# HRT_D_ER100_V1_0.net
KiCad netlist of a schematic drawn in Altium Designer
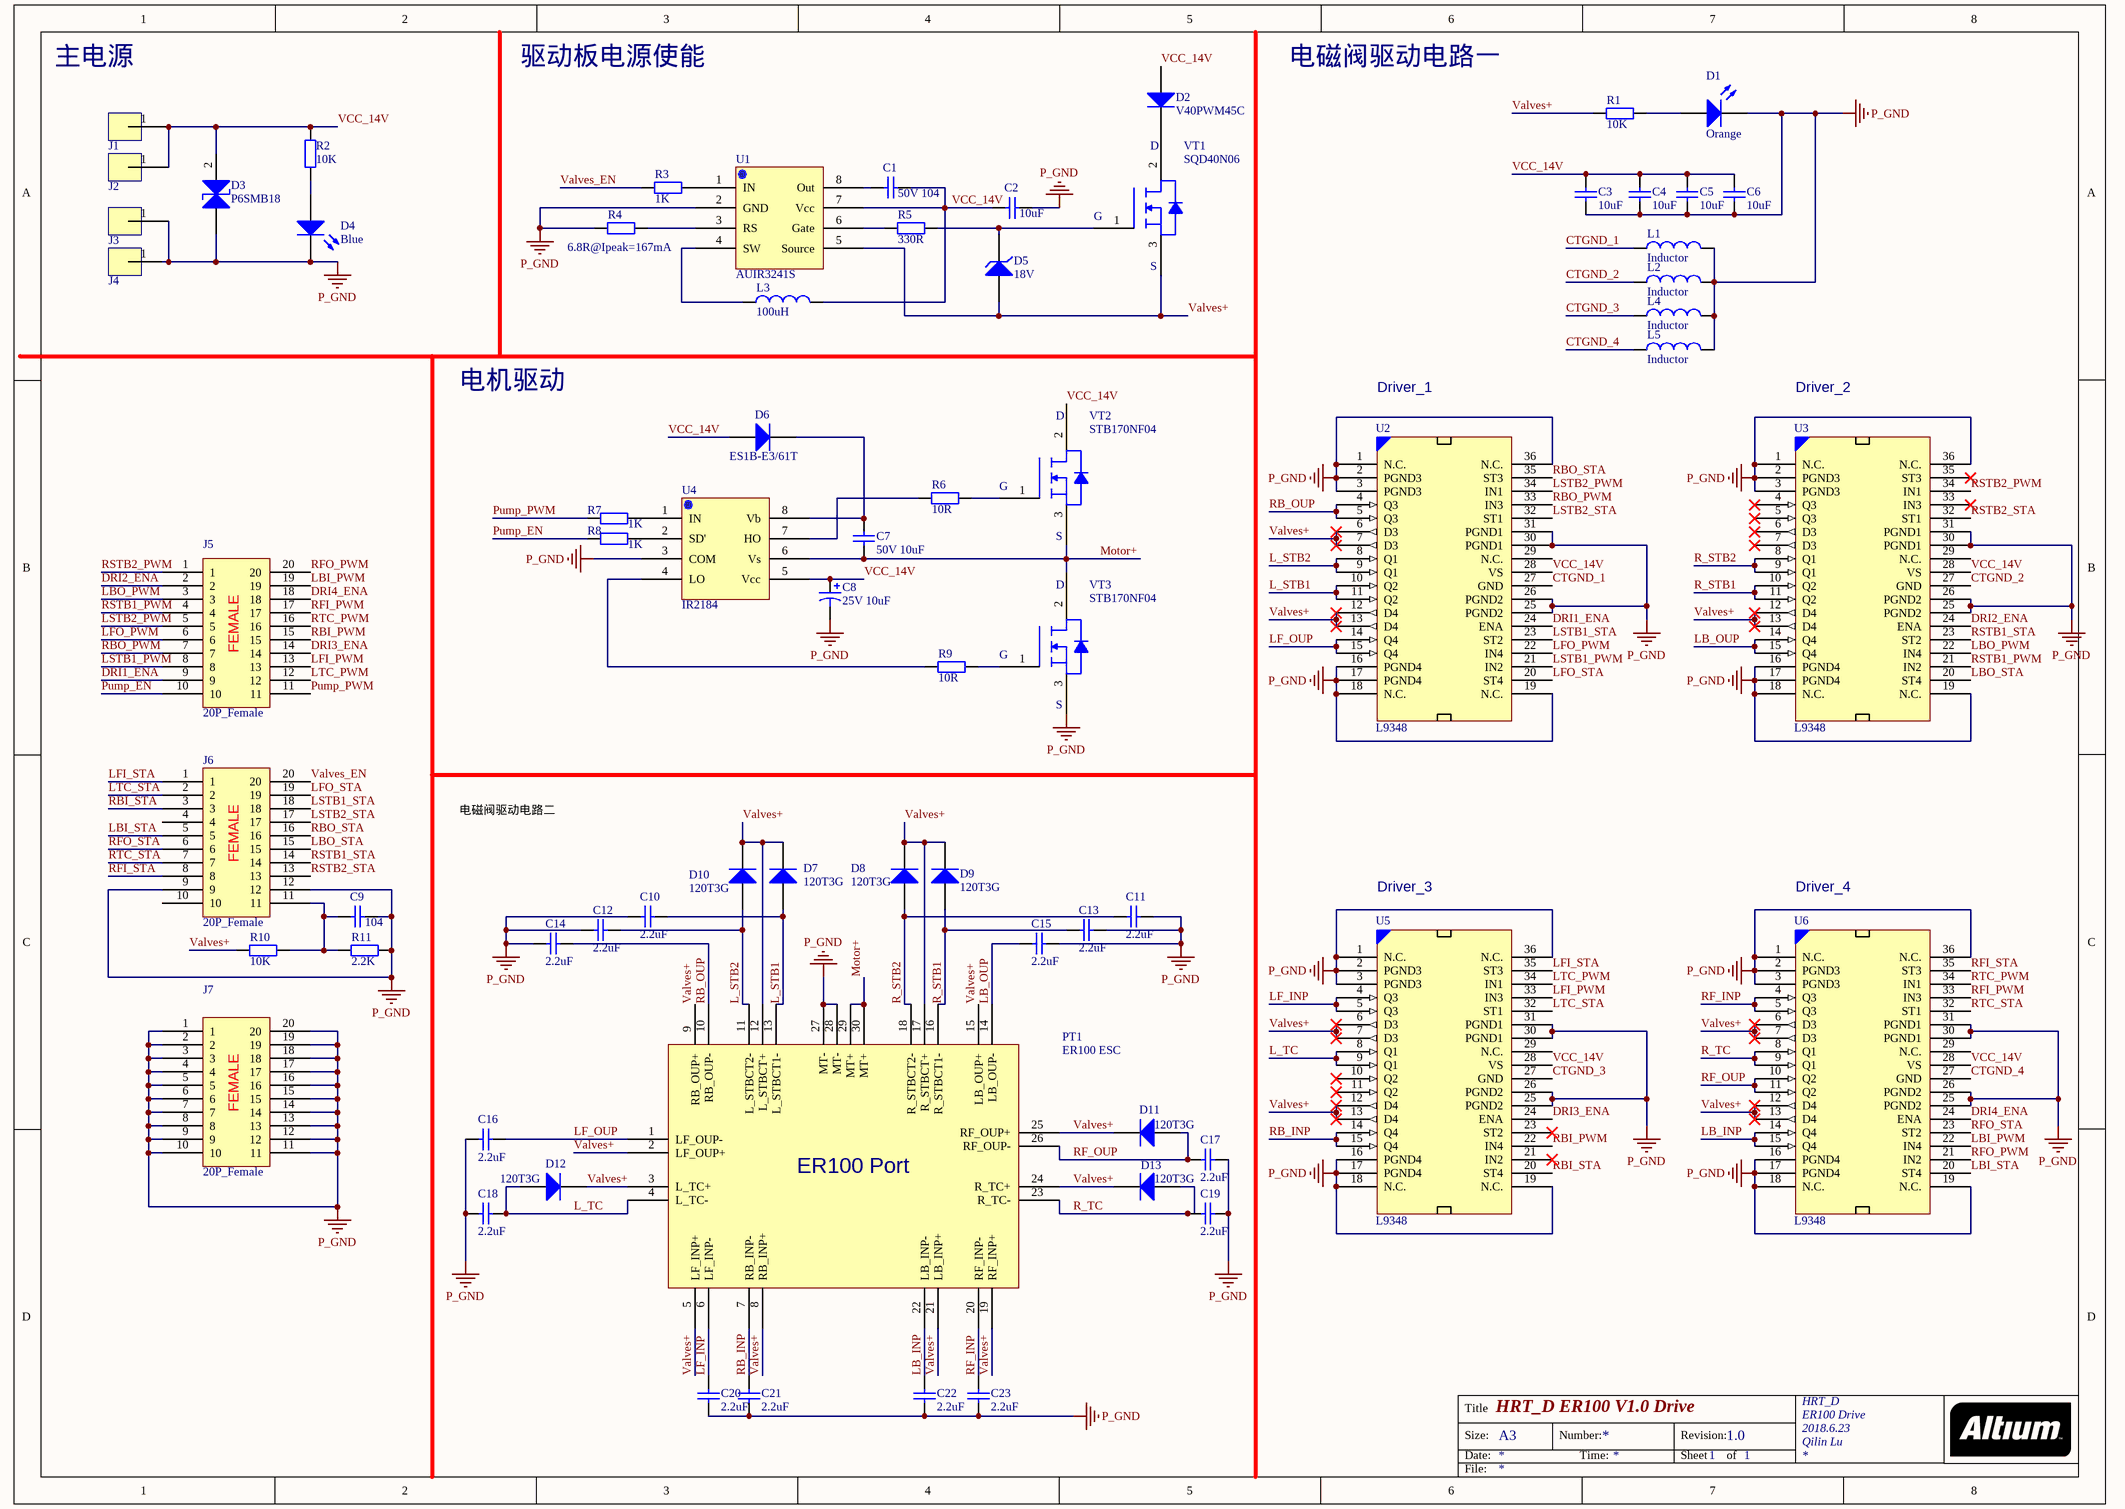
[diagram p0: HRT_D ER100 V1.0.SchDoc]

(export (version "E")
  (design (tool "Eeschema 10.0.6"))
  (components
    (comp (ref "C1")
      (value "50V 104")
      (footprint "C 0805")
      (description "无极性电容")
      (libsource (lib "HRT_D Integrated_Library") (part "Cap"))
    )
    (comp (ref "C2")
      (value "10uF")
      (footprint "C 0805")
      (description "无极性电容")
      (libsource (lib "HRT_D Integrated_Library") (part "Cap"))
    )
    (comp (ref "C3")
      (value "10uF")
      (footprint "C 0805")
      (description "无极性电容")
      (libsource (lib "HRT_D Integrated_Library") (part "Cap"))
    )
    (comp (ref "C4")
      (value "10uF")
      (footprint "C 0805")
      (description "无极性电容")
      (libsource (lib "HRT_D Integrated_Library") (part "Cap"))
    )
    (comp (ref "C5")
      (value "10uF")
      (footprint "C 0805")
      (description "无极性电容")
      (libsource (lib "HRT_D Integrated_Library") (part "Cap"))
    )
    (comp (ref "C6")
      (value "10uF")
      (footprint "C 0805")
      (description "无极性电容")
      (libsource (lib "HRT_D Integrated_Library") (part "Cap"))
    )
    (comp (ref "C7")
      (value "50V 10uF")
      (footprint "C 0805")
      (description "无极性电容")
      (libsource (lib "HRT_D Integrated_Library") (part "Cap"))
    )
    (comp (ref "C8")
      (value "25V 10uF")
      (footprint "CP 3528B")
      (description "极性电容")
      (libsource (lib "HRT_D Integrated_Library") (part "Cap_Pol"))
    )
    (comp (ref "C9")
      (value "104")
      (footprint "C 0805")
      (description "无极性电容")
      (libsource (lib "HRT_D Integrated_Library") (part "Cap"))
    )
    (comp (ref "C10")
      (value "2.2uF")
      (footprint "C 0805")
      (description "无极性电容")
      (libsource (lib "HRT_D Integrated_Library") (part "Cap"))
    )
    (comp (ref "C11")
      (value "2.2uF")
      (footprint "C 0805")
      (description "无极性电容")
      (libsource (lib "HRT_D Integrated_Library") (part "Cap"))
    )
    (comp (ref "C12")
      (value "2.2uF")
      (footprint "C 0805")
      (description "无极性电容")
      (libsource (lib "HRT_D Integrated_Library") (part "Cap"))
    )
    (comp (ref "C13")
      (value "2.2uF")
      (footprint "C 0805")
      (description "无极性电容")
      (libsource (lib "HRT_D Integrated_Library") (part "Cap"))
    )
    (comp (ref "C14")
      (value "2.2uF")
      (footprint "C 0805")
      (description "无极性电容")
      (libsource (lib "HRT_D Integrated_Library") (part "Cap"))
    )
    (comp (ref "C15")
      (value "2.2uF")
      (footprint "C 0805")
      (description "无极性电容")
      (libsource (lib "HRT_D Integrated_Library") (part "Cap"))
    )
    (comp (ref "C16")
      (value "2.2uF")
      (footprint "C 0805")
      (description "无极性电容")
      (libsource (lib "HRT_D Integrated_Library") (part "Cap"))
    )
    (comp (ref "C17")
      (value "2.2uF")
      (footprint "C 0805")
      (description "无极性电容")
      (libsource (lib "HRT_D Integrated_Library") (part "Cap"))
    )
    (comp (ref "C18")
      (value "2.2uF")
      (footprint "C 0805")
      (description "无极性电容")
      (libsource (lib "HRT_D Integrated_Library") (part "Cap"))
    )
    (comp (ref "C19")
      (value "2.2uF")
      (footprint "C 0805")
      (description "无极性电容")
      (libsource (lib "HRT_D Integrated_Library") (part "Cap"))
    )
    (comp (ref "C20")
      (value "2.2uF")
      (footprint "C 0805")
      (description "无极性电容")
      (libsource (lib "HRT_D Integrated_Library") (part "Cap"))
    )
    (comp (ref "C21")
      (value "2.2uF")
      (footprint "C 0805")
      (description "无极性电容")
      (libsource (lib "HRT_D Integrated_Library") (part "Cap"))
    )
    (comp (ref "C22")
      (value "2.2uF")
      (footprint "C 0805")
      (description "无极性电容")
      (libsource (lib "HRT_D Integrated_Library") (part "Cap"))
    )
    (comp (ref "C23")
      (value "2.2uF")
      (footprint "C 0805")
      (description "无极性电容")
      (libsource (lib "HRT_D Integrated_Library") (part "Cap"))
    )
    (comp (ref "D1")
      (value "Orange")
      (footprint "LED_0805")
      (description "发光二极管")
      (libsource (lib "HRT_D Integrated_Library") (part "LED"))
    )
    (comp (ref "D2")
      (value "V40PWM45C")
      (footprint "TO252_DIO")
      (description "二极管")
      (libsource (lib "HRT_D Integrated_Library") (part "Diode"))
    )
    (comp (ref "D3")
      (value "P6SMB18")
      (footprint "DO-214AA")
      (description "BiDir TVS Diode")
      (libsource (lib "HRT_D Integrated_Library") (part "P6SMBXX"))
    )
    (comp (ref "D4")
      (value "Blue")
      (footprint "LED_0805")
      (description "发光二极管")
      (libsource (lib "HRT_D Integrated_Library") (part "LED"))
    )
    (comp (ref "D5")
      (value "18V")
      (footprint "LL34")
      (libsource (lib "HRT_D Integrated_Library") (part "Diode_Zener"))
    )
    (comp (ref "D6")
      (value "ES1B-E3/61T")
      (footprint "DO-214AC")
      (description "二极管")
      (libsource (lib "HRT_D Integrated_Library") (part "Diode"))
    )
    (comp (ref "D7")
      (value "120T3G")
      (footprint "DO-214AC")
      (description "二极管")
      (libsource (lib "HRT_D Integrated_Library") (part "Diode"))
    )
    (comp (ref "D8")
      (value "120T3G")
      (footprint "DO-214AC")
      (description "二极管")
      (libsource (lib "HRT_D Integrated_Library") (part "Diode"))
    )
    (comp (ref "D9")
      (value "120T3G")
      (footprint "DO-214AC")
      (description "二极管")
      (libsource (lib "HRT_D Integrated_Library") (part "Diode"))
    )
    (comp (ref "D10")
      (value "120T3G")
      (footprint "DO-214AC")
      (description "二极管")
      (libsource (lib "HRT_D Integrated_Library") (part "Diode"))
    )
    (comp (ref "D11")
      (value "120T3G")
      (footprint "DO-214AC")
      (description "二极管")
      (libsource (lib "HRT_D Integrated_Library") (part "Diode"))
    )
    (comp (ref "D12")
      (value "120T3G")
      (footprint "DO-214AC")
      (description "二极管")
      (libsource (lib "HRT_D Integrated_Library") (part "Diode"))
    )
    (comp (ref "D13")
      (value "120T3G")
      (footprint "DO-214AC")
      (description "二极管")
      (libsource (lib "HRT_D Integrated_Library") (part "Diode"))
    )
    (comp (ref "J1")
      (value "SMT_Connector")
      (footprint "SMT_Connector")
      (description "表贴接线端")
      (libsource (lib "HRT_D Integrated_Library") (part "SMT_Connector"))
    )
    (comp (ref "J2")
      (value "SMT_Connector")
      (footprint "SMT_Connector")
      (description "表贴接线端")
      (libsource (lib "HRT_D Integrated_Library") (part "SMT_Connector"))
    )
    (comp (ref "J3")
      (value "SMT_Connector")
      (footprint "SMT_Connector")
      (description "表贴接线端")
      (libsource (lib "HRT_D Integrated_Library") (part "SMT_Connector"))
    )
    (comp (ref "J4")
      (value "SMT_Connector")
      (footprint "SMT_Connector")
      (description "表贴接线端")
      (libsource (lib "HRT_D Integrated_Library") (part "SMT_Connector"))
    )
    (comp (ref "J5")
      (value "20P_Female")
      (footprint "B2B_1.27_Female")
      (description "板对板连接器 母头")
      (libsource (lib "HRT_D Integrated_Library") (part "B2B_1.27_Female"))
    )
    (comp (ref "J6")
      (value "20P_Female")
      (footprint "B2B_1.27_Female")
      (description "板对板连接器 母头")
      (libsource (lib "HRT_D Integrated_Library") (part "B2B_1.27_Female"))
    )
    (comp (ref "J7")
      (value "20P_Female")
      (footprint "B2B_1.27_Female")
      (description "板对板连接器 母头")
      (libsource (lib "HRT_D Integrated_Library") (part "B2B_1.27_Female"))
    )
    (comp (ref "L1")
      (value "Inductor")
      (footprint "L 0805")
      (description "电感")
      (libsource (lib "HRT_D Integrated_Library") (part "Inductor"))
    )
    (comp (ref "L2")
      (value "Inductor")
      (footprint "L 0805")
      (description "电感")
      (libsource (lib "HRT_D Integrated_Library") (part "Inductor"))
    )
    (comp (ref "L3")
      (value "100uH")
      (footprint "L 1812")
      (description "电感")
      (libsource (lib "HRT_D Integrated_Library") (part "Inductor"))
    )
    (comp (ref "L4")
      (value "Inductor")
      (footprint "L 0805")
      (description "电感")
      (libsource (lib "HRT_D Integrated_Library") (part "Inductor"))
    )
    (comp (ref "L5")
      (value "Inductor")
      (footprint "L 0805")
      (description "电感")
      (libsource (lib "HRT_D Integrated_Library") (part "Inductor"))
    )
    (comp (ref "PT1")
      (value "ER100 ESC")
      (footprint "ER100 Port")
      (description "ER100元件接口")
      (libsource (lib "HRT_D Integrated_Library") (part "ER100 ESC"))
    )
    (comp (ref "R1")
      (value "10K")
      (footprint "R 0603")
      (description "电阻")
      (libsource (lib "HRT_D Integrated_Library") (part "Resistor"))
    )
    (comp (ref "R2")
      (value "10K")
      (footprint "R 0603")
      (description "电阻")
      (libsource (lib "") (part "Resistor_1"))
    )
    (comp (ref "R3")
      (value "1K")
      (footprint "R 0603")
      (description "电阻")
      (libsource (lib "HRT_D Integrated_Library") (part "Resistor"))
    )
    (comp (ref "R4")
      (value "6.8R@Ipeak=167mA")
      (footprint "R 0805")
      (description "电阻")
      (libsource (lib "HRT_D Integrated_Library") (part "Resistor"))
    )
    (comp (ref "R5")
      (value "330R")
      (footprint "R 0805")
      (description "电阻")
      (libsource (lib "HRT_D Integrated_Library") (part "Resistor"))
    )
    (comp (ref "R6")
      (value "10R")
      (footprint "R 0805")
      (description "电阻")
      (libsource (lib "HRT_D Integrated_Library") (part "Resistor"))
    )
    (comp (ref "R7")
      (value "1K")
      (footprint "R 0603")
      (description "电阻")
      (libsource (lib "HRT_D Integrated_Library") (part "Resistor"))
    )
    (comp (ref "R8")
      (value "1K")
      (footprint "R 0603")
      (description "电阻")
      (libsource (lib "HRT_D Integrated_Library") (part "Resistor"))
    )
    (comp (ref "R9")
      (value "10R")
      (footprint "R 0805")
      (description "电阻")
      (libsource (lib "HRT_D Integrated_Library") (part "Resistor"))
    )
    (comp (ref "R10")
      (value "10K")
      (footprint "R 0805")
      (description "电阻")
      (libsource (lib "") (part "Resistor_2"))
    )
    (comp (ref "R11")
      (value "2.2K")
      (footprint "R 0805")
      (description "电阻")
      (libsource (lib "HRT_D Integrated_Library") (part "Resistor"))
    )
    (comp (ref "U1")
      (value "AUIR3241S")
      (footprint "SOP8")
      (description "B2B MOSFET Driver")
      (libsource (lib "HRT_D Integrated_Library") (part "AUIR3241S"))
    )
    (comp (ref "U2")
      (value "L9348")
      (footprint "PowerSO-36")
      (description "4路电磁阀驱动")
      (libsource (lib "HRT_D Integrated_Library") (part "L9348"))
    )
    (comp (ref "U3")
      (value "L9348")
      (footprint "PowerSO-36")
      (description "4路电磁阀驱动")
      (libsource (lib "HRT_D Integrated_Library") (part "L9348"))
    )
    (comp (ref "U4")
      (value "IR2184")
      (footprint "SOP8")
      (description "Half-Bridge Gate Driver")
      (libsource (lib "HRT_D Integrated_Library") (part "IR2184"))
    )
    (comp (ref "U5")
      (value "L9348")
      (footprint "PowerSO-36")
      (description "4路电磁阀驱动")
      (libsource (lib "HRT_D Integrated_Library") (part "L9348"))
    )
    (comp (ref "U6")
      (value "L9348")
      (footprint "PowerSO-36")
      (description "4路电磁阀驱动")
      (libsource (lib "HRT_D Integrated_Library") (part "L9348"))
    )
    (comp (ref "VT1")
      (value "SQD40N06")
      (footprint "TO252")
      (libsource (lib "HRT_D Integrated_Library") (part "PowerMos_N"))
    )
    (comp (ref "VT2")
      (value "STB170NF04")
      (footprint "TO263-3B")
      (libsource (lib "HRT_D Integrated_Library") (part "PowerMos_N"))
    )
    (comp (ref "VT3")
      (value "STB170NF04")
      (footprint "TO263-3B")
      (libsource (lib "HRT_D Integrated_Library") (part "PowerMos_N"))
    )
  )
  (nets
    (net (code "1") (name "/CTGND_1") (class "Default")
      (node (ref "L1") (pin "1") (pinfunction "1_1") (pintype "passive"))
      (node (ref "U2") (pin "27") (pinfunction "GND_27") (pintype "passive"))
    )
    (net (code "2") (name "/CTGND_2") (class "Default")
      (node (ref "L2") (pin "1") (pinfunction "1_1") (pintype "passive"))
      (node (ref "U3") (pin "27") (pinfunction "GND_27") (pintype "passive"))
    )
    (net (code "3") (name "/CTGND_3") (class "Default")
      (node (ref "L4") (pin "1") (pinfunction "1_1") (pintype "passive"))
      (node (ref "U5") (pin "27") (pinfunction "GND_27") (pintype "passive"))
    )
    (net (code "4") (name "/CTGND_4") (class "Default")
      (node (ref "L5") (pin "1") (pinfunction "1_1") (pintype "passive"))
      (node (ref "U6") (pin "27") (pinfunction "GND_27") (pintype "passive"))
    )
    (net (code "5") (name "/DRI1_ENA") (class "Default")
      (node (ref "J5") (pin "9") (pinfunction "9_9") (pintype "passive"))
      (node (ref "U2") (pin "24") (pinfunction "ENA_24") (pintype "passive"))
    )
    (net (code "6") (name "/DRI2_ENA") (class "Default")
      (node (ref "J5") (pin "2") (pinfunction "2_2") (pintype "passive"))
      (node (ref "U3") (pin "24") (pinfunction "ENA_24") (pintype "passive"))
    )
    (net (code "7") (name "/DRI3_ENA") (class "Default")
      (node (ref "J5") (pin "14") (pinfunction "14_14") (pintype "passive"))
      (node (ref "U5") (pin "24") (pinfunction "ENA_24") (pintype "passive"))
    )
    (net (code "8") (name "/DRI4_ENA") (class "Default")
      (node (ref "J5") (pin "18") (pinfunction "18_18") (pintype "passive"))
      (node (ref "U6") (pin "24") (pinfunction "ENA_24") (pintype "passive"))
    )
    (net (code "9") (name "/LBI_PWM") (class "Default")
      (node (ref "J5") (pin "19") (pinfunction "19_19") (pintype "passive"))
      (node (ref "U6") (pin "22") (pinfunction "IN4_22") (pintype "passive"))
    )
    (net (code "10") (name "/LBI_STA") (class "Default")
      (node (ref "J6") (pin "5") (pinfunction "5_5") (pintype "passive"))
      (node (ref "U6") (pin "20") (pinfunction "ST4_20") (pintype "passive"))
    )
    (net (code "11") (name "/LBO_PWM") (class "Default")
      (node (ref "J5") (pin "3") (pinfunction "3_3") (pintype "passive"))
      (node (ref "U3") (pin "22") (pinfunction "IN4_22") (pintype "passive"))
    )
    (net (code "12") (name "/LBO_STA") (class "Default")
      (node (ref "J6") (pin "15") (pinfunction "15_15") (pintype "passive"))
      (node (ref "U3") (pin "20") (pinfunction "ST4_20") (pintype "passive"))
    )
    (net (code "13") (name "/LB_INP") (class "Default")
      (node (ref "C22") (pin "1") (pinfunction "1_1") (pintype "passive"))
      (node (ref "PT1") (pin "22") (pinfunction "LB_INP-_22") (pintype "passive"))
      (node (ref "U6") (pin "14") (pinfunction "Q4_14") (pintype "input"))
      (node (ref "U6") (pin "15") (pinfunction "Q4_15") (pintype "input"))
    )
    (net (code "14") (name "/LB_OUP") (class "Default")
      (node (ref "C15") (pin "2") (pinfunction "2_2") (pintype "passive"))
      (node (ref "PT1") (pin "14") (pinfunction "LB_OUP-_14") (pintype "passive"))
      (node (ref "U3") (pin "14") (pinfunction "Q4_14") (pintype "input"))
      (node (ref "U3") (pin "15") (pinfunction "Q4_15") (pintype "input"))
    )
    (net (code "15") (name "/LFI_PWM") (class "Default")
      (node (ref "J5") (pin "13") (pinfunction "13_13") (pintype "passive"))
      (node (ref "U5") (pin "33") (pinfunction "IN3_33") (pintype "passive"))
    )
    (net (code "16") (name "/LFI_STA") (class "Default")
      (node (ref "J6") (pin "1") (pinfunction "1_1") (pintype "passive"))
      (node (ref "U5") (pin "35") (pinfunction "ST3_35") (pintype "passive"))
    )
    (net (code "17") (name "/LFO_PWM") (class "Default")
      (node (ref "J5") (pin "6") (pinfunction "6_6") (pintype "passive"))
      (node (ref "U2") (pin "22") (pinfunction "IN4_22") (pintype "passive"))
    )
    (net (code "18") (name "/LFO_STA") (class "Default")
      (node (ref "J6") (pin "19") (pinfunction "19_19") (pintype "passive"))
      (node (ref "U2") (pin "20") (pinfunction "ST4_20") (pintype "passive"))
    )
    (net (code "19") (name "/LF_INP") (class "Default")
      (node (ref "C20") (pin "1") (pinfunction "1_1") (pintype "passive"))
      (node (ref "PT1") (pin "6") (pinfunction "LF_INP-_6") (pintype "passive"))
      (node (ref "U5") (pin "4") (pinfunction "Q3_4") (pintype "input"))
      (node (ref "U5") (pin "5") (pinfunction "Q3_5") (pintype "input"))
    )
    (net (code "20") (name "/LF_OUP") (class "Default")
      (node (ref "C16") (pin "1") (pinfunction "1_1") (pintype "passive"))
      (node (ref "PT1") (pin "1") (pinfunction "LF_OUP-_1") (pintype "passive"))
      (node (ref "U2") (pin "14") (pinfunction "Q4_14") (pintype "input"))
      (node (ref "U2") (pin "15") (pinfunction "Q4_15") (pintype "input"))
    )
    (net (code "21") (name "/LSTB1_PWM") (class "Default")
      (node (ref "J5") (pin "8") (pinfunction "8_8") (pintype "passive"))
      (node (ref "U2") (pin "21") (pinfunction "IN2_21") (pintype "passive"))
    )
    (net (code "22") (name "/LSTB1_STA") (class "Default")
      (node (ref "J6") (pin "18") (pinfunction "18_18") (pintype "passive"))
      (node (ref "U2") (pin "23") (pinfunction "ST2_23") (pintype "passive"))
    )
    (net (code "23") (name "/LSTB2_PWM") (class "Default")
      (node (ref "J5") (pin "5") (pinfunction "5_5") (pintype "passive"))
      (node (ref "U2") (pin "34") (pinfunction "IN1_34") (pintype "passive"))
    )
    (net (code "24") (name "/LSTB2_STA") (class "Default")
      (node (ref "J6") (pin "17") (pinfunction "17_17") (pintype "passive"))
      (node (ref "U2") (pin "32") (pinfunction "ST1_32") (pintype "passive"))
    )
    (net (code "25") (name "/LTC_PWM") (class "Default")
      (node (ref "J5") (pin "12") (pinfunction "12_12") (pintype "passive"))
      (node (ref "U5") (pin "34") (pinfunction "IN1_34") (pintype "passive"))
    )
    (net (code "26") (name "/LTC_STA") (class "Default")
      (node (ref "J6") (pin "2") (pinfunction "2_2") (pintype "passive"))
      (node (ref "U5") (pin "32") (pinfunction "ST1_32") (pintype "passive"))
    )
    (net (code "27") (name "/L_STB1") (class "Default")
      (node (ref "C10") (pin "1") (pinfunction "1_1") (pintype "passive"))
      (node (ref "D7") (pin "1") (pinfunction "A_1") (pintype "passive"))
      (node (ref "PT1") (pin "13") (pinfunction "L_STBCT1-_13") (pintype "passive"))
      (node (ref "U2") (pin "10") (pinfunction "Q2_10") (pintype "input"))
      (node (ref "U2") (pin "11") (pinfunction "Q2_11") (pintype "input"))
    )
    (net (code "28") (name "/L_STB2") (class "Default")
      (node (ref "C12") (pin "1") (pinfunction "1_1") (pintype "passive"))
      (node (ref "D10") (pin "1") (pinfunction "A_1") (pintype "passive"))
      (node (ref "PT1") (pin "11") (pinfunction "L_STBCT2-_11") (pintype "passive"))
      (node (ref "U2") (pin "8") (pinfunction "Q1_8") (pintype "input"))
      (node (ref "U2") (pin "9") (pinfunction "Q1_9") (pintype "input"))
    )
    (net (code "29") (name "/L_TC") (class "Default")
      (node (ref "C18") (pin "1") (pinfunction "1_1") (pintype "passive"))
      (node (ref "D12") (pin "1") (pinfunction "A_1") (pintype "passive"))
      (node (ref "PT1") (pin "4") (pinfunction "L_TC-_4") (pintype "passive"))
      (node (ref "U5") (pin "8") (pinfunction "Q1_8") (pintype "input"))
      (node (ref "U5") (pin "9") (pinfunction "Q1_9") (pintype "input"))
    )
    (net (code "30") (name "/Motor+") (class "Default")
      (node (ref "C7") (pin "2") (pinfunction "2_2") (pintype "passive"))
      (node (ref "PT1") (pin "29") (pinfunction "MT+_29") (pintype "passive"))
      (node (ref "PT1") (pin "30") (pinfunction "MT+_30") (pintype "passive"))
      (node (ref "U4") (pin "6") (pinfunction "Vs_6") (pintype "passive"))
      (node (ref "VT2") (pin "3") (pinfunction "3_3") (pintype "passive"))
      (node (ref "VT3") (pin "2") (pinfunction "2_2") (pintype "passive"))
    )
    (net (code "31") (name "/Pump_EN") (class "Default")
      (node (ref "J5") (pin "10") (pinfunction "10_10") (pintype "passive"))
      (node (ref "R8") (pin "1") (pinfunction "1_1") (pintype "passive"))
    )
    (net (code "32") (name "/Pump_PWM") (class "Default")
      (node (ref "J5") (pin "11") (pinfunction "11_11") (pintype "passive"))
      (node (ref "R7") (pin "1") (pinfunction "1_1") (pintype "passive"))
    )
    (net (code "33") (name "/RBI_PWM") (class "Default")
      (node (ref "J5") (pin "15") (pinfunction "15_15") (pintype "passive"))
      (node (ref "U5") (pin "22") (pinfunction "IN4_22") (pintype "passive"))
    )
    (net (code "34") (name "/RBI_STA") (class "Default")
      (node (ref "J6") (pin "3") (pinfunction "3_3") (pintype "passive"))
      (node (ref "U5") (pin "20") (pinfunction "ST4_20") (pintype "passive"))
    )
    (net (code "35") (name "/RBO_PWM") (class "Default")
      (node (ref "J5") (pin "7") (pinfunction "7_7") (pintype "passive"))
      (node (ref "U2") (pin "33") (pinfunction "IN3_33") (pintype "passive"))
    )
    (net (code "36") (name "/RBO_STA") (class "Default")
      (node (ref "J6") (pin "16") (pinfunction "16_16") (pintype "passive"))
      (node (ref "U2") (pin "35") (pinfunction "ST3_35") (pintype "passive"))
    )
    (net (code "37") (name "/RB_INP") (class "Default")
      (node (ref "C21") (pin "1") (pinfunction "1_1") (pintype "passive"))
      (node (ref "PT1") (pin "7") (pinfunction "RB_INP-_7") (pintype "passive"))
      (node (ref "U5") (pin "14") (pinfunction "Q4_14") (pintype "input"))
      (node (ref "U5") (pin "15") (pinfunction "Q4_15") (pintype "input"))
    )
    (net (code "38") (name "/RB_OUP") (class "Default")
      (node (ref "C14") (pin "1") (pinfunction "1_1") (pintype "passive"))
      (node (ref "PT1") (pin "10") (pinfunction "RB_OUP-_10") (pintype "passive"))
      (node (ref "U2") (pin "4") (pinfunction "Q3_4") (pintype "input"))
      (node (ref "U2") (pin "5") (pinfunction "Q3_5") (pintype "input"))
    )
    (net (code "39") (name "/RFI_PWM") (class "Default")
      (node (ref "J5") (pin "17") (pinfunction "17_17") (pintype "passive"))
      (node (ref "U6") (pin "33") (pinfunction "IN3_33") (pintype "passive"))
    )
    (net (code "40") (name "/RFI_STA") (class "Default")
      (node (ref "J6") (pin "8") (pinfunction "8_8") (pintype "passive"))
      (node (ref "U6") (pin "35") (pinfunction "ST3_35") (pintype "passive"))
    )
    (net (code "41") (name "/RFO_PWM") (class "Default")
      (node (ref "J5") (pin "20") (pinfunction "20_20") (pintype "passive"))
      (node (ref "U6") (pin "21") (pinfunction "IN2_21") (pintype "passive"))
    )
    (net (code "42") (name "/RFO_STA") (class "Default")
      (node (ref "J6") (pin "6") (pinfunction "6_6") (pintype "passive"))
      (node (ref "U6") (pin "23") (pinfunction "ST2_23") (pintype "passive"))
    )
    (net (code "43") (name "/RF_INP") (class "Default")
      (node (ref "C23") (pin "1") (pinfunction "1_1") (pintype "passive"))
      (node (ref "PT1") (pin "20") (pinfunction "RF_INP-_20") (pintype "passive"))
      (node (ref "U6") (pin "4") (pinfunction "Q3_4") (pintype "input"))
      (node (ref "U6") (pin "5") (pinfunction "Q3_5") (pintype "input"))
    )
    (net (code "44") (name "/RF_OUP") (class "Default")
      (node (ref "C17") (pin "2") (pinfunction "2_2") (pintype "passive"))
      (node (ref "D11") (pin "1") (pinfunction "A_1") (pintype "passive"))
      (node (ref "PT1") (pin "26") (pinfunction "RF_OUP-_26") (pintype "passive"))
      (node (ref "U6") (pin "10") (pinfunction "Q2_10") (pintype "input"))
      (node (ref "U6") (pin "11") (pinfunction "Q2_11") (pintype "input"))
    )
    (net (code "45") (name "/RSTB1_PWM") (class "Default")
      (node (ref "J5") (pin "4") (pinfunction "4_4") (pintype "passive"))
      (node (ref "U3") (pin "21") (pinfunction "IN2_21") (pintype "passive"))
    )
    (net (code "46") (name "/RSTB1_STA") (class "Default")
      (node (ref "J6") (pin "14") (pinfunction "14_14") (pintype "passive"))
      (node (ref "U3") (pin "23") (pinfunction "ST2_23") (pintype "passive"))
    )
    (net (code "47") (name "/RSTB2_PWM") (class "Default")
      (node (ref "J5") (pin "1") (pinfunction "1_1") (pintype "passive"))
      (node (ref "U3") (pin "34") (pinfunction "IN1_34") (pintype "passive"))
    )
    (net (code "48") (name "/RSTB2_STA") (class "Default")
      (node (ref "J6") (pin "13") (pinfunction "13_13") (pintype "passive"))
      (node (ref "U3") (pin "32") (pinfunction "ST1_32") (pintype "passive"))
    )
    (net (code "49") (name "/RTC_PWM") (class "Default")
      (node (ref "J5") (pin "16") (pinfunction "16_16") (pintype "passive"))
      (node (ref "U6") (pin "34") (pinfunction "IN1_34") (pintype "passive"))
    )
    (net (code "50") (name "/RTC_STA") (class "Default")
      (node (ref "J6") (pin "7") (pinfunction "7_7") (pintype "passive"))
      (node (ref "U6") (pin "32") (pinfunction "ST1_32") (pintype "passive"))
    )
    (net (code "51") (name "/R_STB1") (class "Default")
      (node (ref "C13") (pin "2") (pinfunction "2_2") (pintype "passive"))
      (node (ref "D9") (pin "1") (pinfunction "A_1") (pintype "passive"))
      (node (ref "PT1") (pin "16") (pinfunction "R_STBCT1-_16") (pintype "passive"))
      (node (ref "U3") (pin "10") (pinfunction "Q2_10") (pintype "input"))
      (node (ref "U3") (pin "11") (pinfunction "Q2_11") (pintype "input"))
    )
    (net (code "52") (name "/R_STB2") (class "Default")
      (node (ref "C11") (pin "2") (pinfunction "2_2") (pintype "passive"))
      (node (ref "D8") (pin "1") (pinfunction "A_1") (pintype "passive"))
      (node (ref "PT1") (pin "18") (pinfunction "R_STBCT2-_18") (pintype "passive"))
      (node (ref "U3") (pin "8") (pinfunction "Q1_8") (pintype "input"))
      (node (ref "U3") (pin "9") (pinfunction "Q1_9") (pintype "input"))
    )
    (net (code "53") (name "/R_TC") (class "Default")
      (node (ref "C19") (pin "2") (pinfunction "2_2") (pintype "passive"))
      (node (ref "D13") (pin "1") (pinfunction "A_1") (pintype "passive"))
      (node (ref "PT1") (pin "23") (pinfunction "R_TC-_23") (pintype "passive"))
      (node (ref "U6") (pin "8") (pinfunction "Q1_8") (pintype "input"))
      (node (ref "U6") (pin "9") (pinfunction "Q1_9") (pintype "input"))
    )
    (net (code "54") (name "/VCC_14V") (class "Default")
      (node (ref "C1") (pin "2") (pinfunction "2_2") (pintype "passive"))
      (node (ref "C2") (pin "2") (pinfunction "2_2") (pintype "passive"))
      (node (ref "C3") (pin "1") (pinfunction "1_1") (pintype "passive"))
      (node (ref "C4") (pin "1") (pinfunction "1_1") (pintype "passive"))
      (node (ref "C5") (pin "1") (pinfunction "1_1") (pintype "passive"))
      (node (ref "C6") (pin "1") (pinfunction "1_1") (pintype "passive"))
      (node (ref "C8") (pin "1") (pinfunction "1_1") (pintype "passive"))
      (node (ref "D2") (pin "1") (pinfunction "A_1") (pintype "passive"))
      (node (ref "D3") (pin "2") (pinfunction "K_2") (pintype "passive"))
      (node (ref "D6") (pin "1") (pinfunction "A_1") (pintype "passive"))
      (node (ref "J1") (pin "1") (pinfunction "1_1") (pintype "passive"))
      (node (ref "J2") (pin "1") (pinfunction "1_1") (pintype "passive"))
      (node (ref "L3") (pin "2") (pinfunction "2_2") (pintype "passive"))
      (node (ref "R2") (pin "2") (pinfunction "2_2") (pintype "passive"))
      (node (ref "U1") (pin "7") (pinfunction "Vcc_7") (pintype "passive"))
      (node (ref "U2") (pin "28") (pinfunction "VS_28") (pintype "passive"))
      (node (ref "U3") (pin "28") (pinfunction "VS_28") (pintype "passive"))
      (node (ref "U4") (pin "5") (pinfunction "Vcc_5") (pintype "passive"))
      (node (ref "U5") (pin "28") (pinfunction "VS_28") (pintype "passive"))
      (node (ref "U6") (pin "28") (pinfunction "VS_28") (pintype "passive"))
      (node (ref "VT2") (pin "2") (pinfunction "2_2") (pintype "passive"))
    )
    (net (code "55") (name "/Valves+") (class "Default")
      (node (ref "D10") (pin "2") (pinfunction "K_2") (pintype "passive"))
      (node (ref "D11") (pin "2") (pinfunction "K_2") (pintype "passive"))
      (node (ref "D12") (pin "2") (pinfunction "K_2") (pintype "passive"))
      (node (ref "D13") (pin "2") (pinfunction "K_2") (pintype "passive"))
      (node (ref "D5") (pin "1") (pinfunction "A_1") (pintype "passive"))
      (node (ref "D7") (pin "2") (pinfunction "K_2") (pintype "passive"))
      (node (ref "D8") (pin "2") (pinfunction "K_2") (pintype "passive"))
      (node (ref "D9") (pin "2") (pinfunction "K_2") (pintype "passive"))
      (node (ref "PT1") (pin "12") (pinfunction "L_STBCT+_12") (pintype "passive"))
      (node (ref "PT1") (pin "15") (pinfunction "LB_OUP+_15") (pintype "passive"))
      (node (ref "PT1") (pin "17") (pinfunction "R_STBCT+_17") (pintype "passive"))
      (node (ref "PT1") (pin "19") (pinfunction "RF_INP+_19") (pintype "passive"))
      (node (ref "PT1") (pin "2") (pinfunction "LF_OUP+_2") (pintype "passive"))
      (node (ref "PT1") (pin "21") (pinfunction "LB_INP+_21") (pintype "passive"))
      (node (ref "PT1") (pin "24") (pinfunction "R_TC+_24") (pintype "passive"))
      (node (ref "PT1") (pin "25") (pinfunction "RF_OUP+_25") (pintype "passive"))
      (node (ref "PT1") (pin "3") (pinfunction "L_TC+_3") (pintype "passive"))
      (node (ref "PT1") (pin "5") (pinfunction "LF_INP+_5") (pintype "passive"))
      (node (ref "PT1") (pin "8") (pinfunction "RB_INP+_8") (pintype "passive"))
      (node (ref "PT1") (pin "9") (pinfunction "RB_OUP+_9") (pintype "passive"))
      (node (ref "R1") (pin "1") (pinfunction "1_1") (pintype "passive"))
      (node (ref "R10") (pin "2") (pinfunction "2_2") (pintype "passive"))
      (node (ref "U1") (pin "5") (pinfunction "Source_5") (pintype "passive"))
      (node (ref "U2") (pin "12") (pinfunction "D4_12") (pintype "output"))
      (node (ref "U2") (pin "13") (pinfunction "D4_13") (pintype "output"))
      (node (ref "U2") (pin "6") (pinfunction "D3_6") (pintype "output"))
      (node (ref "U2") (pin "7") (pinfunction "D3_7") (pintype "output"))
      (node (ref "U3") (pin "12") (pinfunction "D4_12") (pintype "output"))
      (node (ref "U3") (pin "13") (pinfunction "D4_13") (pintype "output"))
      (node (ref "U5") (pin "12") (pinfunction "D4_12") (pintype "output"))
      (node (ref "U5") (pin "13") (pinfunction "D4_13") (pintype "output"))
      (node (ref "U5") (pin "6") (pinfunction "D3_6") (pintype "output"))
      (node (ref "U5") (pin "7") (pinfunction "D3_7") (pintype "output"))
      (node (ref "U6") (pin "12") (pinfunction "D4_12") (pintype "output"))
      (node (ref "U6") (pin "13") (pinfunction "D4_13") (pintype "output"))
      (node (ref "U6") (pin "6") (pinfunction "D3_6") (pintype "output"))
      (node (ref "U6") (pin "7") (pinfunction "D3_7") (pintype "output"))
      (node (ref "VT1") (pin "3") (pinfunction "3_3") (pintype "passive"))
    )
    (net (code "56") (name "/Valves_EN") (class "Default")
      (node (ref "J6") (pin "20") (pinfunction "20_20") (pintype "passive"))
      (node (ref "R3") (pin "1") (pinfunction "1_1") (pintype "passive"))
    )
    (net (code "57") (name "Net-(C9-Pad2)") (class "Default")
      (node (ref "C9") (pin "2") (pinfunction "2_2") (pintype "passive"))
      (node (ref "J6") (pin "11") (pinfunction "11_11") (pintype "passive"))
      (node (ref "R10") (pin "1") (pinfunction "1_1") (pintype "passive"))
      (node (ref "R11") (pin "1") (pinfunction "1_1") (pintype "passive"))
    )
    (net (code "58") (name "Net-(D1-A)") (class "Default")
      (node (ref "D1") (pin "1") (pinfunction "A_1") (pintype "passive"))
      (node (ref "R1") (pin "2") (pinfunction "2_2") (pintype "passive"))
    )
    (net (code "59") (name "Net-(D2-K)") (class "Default")
      (node (ref "D2") (pin "2") (pinfunction "K_2") (pintype "passive"))
      (node (ref "VT1") (pin "2") (pinfunction "2_2") (pintype "passive"))
    )
    (net (code "60") (name "Net-(D4-A)") (class "Default")
      (node (ref "D4") (pin "1") (pinfunction "A_1") (pintype "passive"))
      (node (ref "R2") (pin "1") (pinfunction "1_1") (pintype "passive"))
    )
    (net (code "61") (name "Net-(D5-K)") (class "Default")
      (node (ref "D5") (pin "2") (pinfunction "K_2") (pintype "passive"))
      (node (ref "R5") (pin "2") (pinfunction "2_2") (pintype "passive"))
      (node (ref "VT1") (pin "1") (pinfunction "G_1") (pintype "passive"))
    )
    (net (code "62") (name "Net-(D6-K)") (class "Default")
      (node (ref "C7") (pin "1") (pinfunction "1_1") (pintype "passive"))
      (node (ref "D6") (pin "2") (pinfunction "K_2") (pintype "passive"))
      (node (ref "U4") (pin "8") (pinfunction "Vb_8") (pintype "passive"))
    )
    (net (code "63") (name "Net-(U1-Gate)") (class "Default")
      (node (ref "R5") (pin "1") (pinfunction "1_1") (pintype "passive"))
      (node (ref "U1") (pin "6") (pinfunction "Gate_6") (pintype "passive"))
    )
    (net (code "64") (name "Net-(U1-IN)") (class "Default")
      (node (ref "R3") (pin "2") (pinfunction "2_2") (pintype "passive"))
      (node (ref "U1") (pin "1") (pinfunction "IN_1") (pintype "passive"))
    )
    (net (code "65") (name "Net-(U1-Out)") (class "Default")
      (node (ref "C1") (pin "1") (pinfunction "1_1") (pintype "passive"))
      (node (ref "U1") (pin "8") (pinfunction "Out_8") (pintype "passive"))
    )
    (net (code "66") (name "Net-(U1-RS)") (class "Default")
      (node (ref "R4") (pin "2") (pinfunction "2_2") (pintype "passive"))
      (node (ref "U1") (pin "3") (pinfunction "RS_3") (pintype "passive"))
    )
    (net (code "67") (name "Net-(U1-SW)") (class "Default")
      (node (ref "L3") (pin "1") (pinfunction "1_1") (pintype "passive"))
      (node (ref "U1") (pin "4") (pinfunction "SW_4") (pintype "passive"))
    )
    (net (code "68") (name "Net-(U4-HO)") (class "Default")
      (node (ref "R6") (pin "1") (pinfunction "1_1") (pintype "passive"))
      (node (ref "U4") (pin "7") (pinfunction "HO_7") (pintype "passive"))
    )
    (net (code "69") (name "Net-(U4-IN)") (class "Default")
      (node (ref "R7") (pin "2") (pinfunction "2_2") (pintype "passive"))
      (node (ref "U4") (pin "1") (pinfunction "IN_1") (pintype "passive"))
    )
    (net (code "70") (name "Net-(U4-LO)") (class "Default")
      (node (ref "R9") (pin "1") (pinfunction "1_1") (pintype "passive"))
      (node (ref "U4") (pin "4") (pinfunction "LO_4") (pintype "passive"))
    )
    (net (code "71") (name "Net-(U4-SD')") (class "Default")
      (node (ref "R8") (pin "2") (pinfunction "2_2") (pintype "passive"))
      (node (ref "U4") (pin "2") (pinfunction "SD'_2") (pintype "passive"))
    )
    (net (code "72") (name "Net-(VT2-G)") (class "Default")
      (node (ref "R6") (pin "2") (pinfunction "2_2") (pintype "passive"))
      (node (ref "VT2") (pin "1") (pinfunction "G_1") (pintype "passive"))
    )
    (net (code "73") (name "Net-(VT3-G)") (class "Default")
      (node (ref "R9") (pin "2") (pinfunction "2_2") (pintype "passive"))
      (node (ref "VT3") (pin "1") (pinfunction "G_1") (pintype "passive"))
    )
    (net (code "74") (name "P_GND") (class "Default")
      (node (ref "C10") (pin "2") (pinfunction "2_2") (pintype "passive"))
      (node (ref "C11") (pin "1") (pinfunction "1_1") (pintype "passive"))
      (node (ref "C12") (pin "2") (pinfunction "2_2") (pintype "passive"))
      (node (ref "C13") (pin "1") (pinfunction "1_1") (pintype "passive"))
      (node (ref "C14") (pin "2") (pinfunction "2_2") (pintype "passive"))
      (node (ref "C15") (pin "1") (pinfunction "1_1") (pintype "passive"))
      (node (ref "C16") (pin "2") (pinfunction "2_2") (pintype "passive"))
      (node (ref "C17") (pin "1") (pinfunction "1_1") (pintype "passive"))
      (node (ref "C18") (pin "2") (pinfunction "2_2") (pintype "passive"))
      (node (ref "C19") (pin "1") (pinfunction "1_1") (pintype "passive"))
      (node (ref "C2") (pin "1") (pinfunction "1_1") (pintype "passive"))
      (node (ref "C20") (pin "2") (pinfunction "2_2") (pintype "passive"))
      (node (ref "C21") (pin "2") (pinfunction "2_2") (pintype "passive"))
      (node (ref "C22") (pin "2") (pinfunction "2_2") (pintype "passive"))
      (node (ref "C23") (pin "2") (pinfunction "2_2") (pintype "passive"))
      (node (ref "C3") (pin "2") (pinfunction "2_2") (pintype "passive"))
      (node (ref "C4") (pin "2") (pinfunction "2_2") (pintype "passive"))
      (node (ref "C5") (pin "2") (pinfunction "2_2") (pintype "passive"))
      (node (ref "C6") (pin "2") (pinfunction "2_2") (pintype "passive"))
      (node (ref "C8") (pin "2") (pinfunction "2_2") (pintype "passive"))
      (node (ref "C9") (pin "1") (pinfunction "1_1") (pintype "passive"))
      (node (ref "D1") (pin "2") (pinfunction "K_2") (pintype "passive"))
      (node (ref "D3") (pin "1") (pinfunction "A_1") (pintype "passive"))
      (node (ref "D4") (pin "2") (pinfunction "K_2") (pintype "passive"))
      (node (ref "J3") (pin "1") (pinfunction "1_1") (pintype "passive"))
      (node (ref "J4") (pin "1") (pinfunction "1_1") (pintype "passive"))
      (node (ref "J6") (pin "12") (pinfunction "12_12") (pintype "passive"))
      (node (ref "J6") (pin "9") (pinfunction "9_9") (pintype "passive"))
      (node (ref "J7") (pin "1") (pinfunction "1_1") (pintype "passive"))
      (node (ref "J7") (pin "10") (pinfunction "10_10") (pintype "passive"))
      (node (ref "J7") (pin "11") (pinfunction "11_11") (pintype "passive"))
      (node (ref "J7") (pin "12") (pinfunction "12_12") (pintype "passive"))
      (node (ref "J7") (pin "13") (pinfunction "13_13") (pintype "passive"))
      (node (ref "J7") (pin "14") (pinfunction "14_14") (pintype "passive"))
      (node (ref "J7") (pin "15") (pinfunction "15_15") (pintype "passive"))
      (node (ref "J7") (pin "16") (pinfunction "16_16") (pintype "passive"))
      (node (ref "J7") (pin "17") (pinfunction "17_17") (pintype "passive"))
      (node (ref "J7") (pin "18") (pinfunction "18_18") (pintype "passive"))
      (node (ref "J7") (pin "19") (pinfunction "19_19") (pintype "passive"))
      (node (ref "J7") (pin "2") (pinfunction "2_2") (pintype "passive"))
      (node (ref "J7") (pin "20") (pinfunction "20_20") (pintype "passive"))
      (node (ref "J7") (pin "3") (pinfunction "3_3") (pintype "passive"))
      (node (ref "J7") (pin "4") (pinfunction "4_4") (pintype "passive"))
      (node (ref "J7") (pin "5") (pinfunction "5_5") (pintype "passive"))
      (node (ref "J7") (pin "6") (pinfunction "6_6") (pintype "passive"))
      (node (ref "J7") (pin "7") (pinfunction "7_7") (pintype "passive"))
      (node (ref "J7") (pin "8") (pinfunction "8_8") (pintype "passive"))
      (node (ref "J7") (pin "9") (pinfunction "9_9") (pintype "passive"))
      (node (ref "L1") (pin "2") (pinfunction "2_2") (pintype "passive"))
      (node (ref "L2") (pin "2") (pinfunction "2_2") (pintype "passive"))
      (node (ref "L4") (pin "2") (pinfunction "2_2") (pintype "passive"))
      (node (ref "L5") (pin "2") (pinfunction "2_2") (pintype "passive"))
      (node (ref "PT1") (pin "27") (pinfunction "MT-_27") (pintype "passive"))
      (node (ref "PT1") (pin "28") (pinfunction "MT-_28") (pintype "passive"))
      (node (ref "R11") (pin "2") (pinfunction "2_2") (pintype "passive"))
      (node (ref "R4") (pin "1") (pinfunction "1_1") (pintype "passive"))
      (node (ref "U1") (pin "2") (pinfunction "GND_2") (pintype "passive"))
      (node (ref "U2") (pin "1") (pinfunction "N.C._1") (pintype "passive"))
      (node (ref "U2") (pin "16") (pinfunction "PGND4_16") (pintype "passive"))
      (node (ref "U2") (pin "17") (pinfunction "PGND4_17") (pintype "passive"))
      (node (ref "U2") (pin "18") (pinfunction "N.C._18") (pintype "passive"))
      (node (ref "U2") (pin "19") (pinfunction "N.C._19") (pintype "passive"))
      (node (ref "U2") (pin "2") (pinfunction "PGND3_2") (pintype "passive"))
      (node (ref "U2") (pin "25") (pinfunction "PGND2_25") (pintype "passive"))
      (node (ref "U2") (pin "26") (pinfunction "PGND2_26") (pintype "passive"))
      (node (ref "U2") (pin "3") (pinfunction "PGND3_3") (pintype "passive"))
      (node (ref "U2") (pin "30") (pinfunction "PGND1_30") (pintype "passive"))
      (node (ref "U2") (pin "31") (pinfunction "PGND1_31") (pintype "passive"))
      (node (ref "U2") (pin "36") (pinfunction "N.C._36") (pintype "passive"))
      (node (ref "U3") (pin "1") (pinfunction "N.C._1") (pintype "passive"))
      (node (ref "U3") (pin "16") (pinfunction "PGND4_16") (pintype "passive"))
      (node (ref "U3") (pin "17") (pinfunction "PGND4_17") (pintype "passive"))
      (node (ref "U3") (pin "18") (pinfunction "N.C._18") (pintype "passive"))
      (node (ref "U3") (pin "19") (pinfunction "N.C._19") (pintype "passive"))
      (node (ref "U3") (pin "2") (pinfunction "PGND3_2") (pintype "passive"))
      (node (ref "U3") (pin "25") (pinfunction "PGND2_25") (pintype "passive"))
      (node (ref "U3") (pin "26") (pinfunction "PGND2_26") (pintype "passive"))
      (node (ref "U3") (pin "3") (pinfunction "PGND3_3") (pintype "passive"))
      (node (ref "U3") (pin "30") (pinfunction "PGND1_30") (pintype "passive"))
      (node (ref "U3") (pin "31") (pinfunction "PGND1_31") (pintype "passive"))
      (node (ref "U3") (pin "36") (pinfunction "N.C._36") (pintype "passive"))
      (node (ref "U4") (pin "3") (pinfunction "COM_3") (pintype "passive"))
      (node (ref "U5") (pin "1") (pinfunction "N.C._1") (pintype "passive"))
      (node (ref "U5") (pin "16") (pinfunction "PGND4_16") (pintype "passive"))
      (node (ref "U5") (pin "17") (pinfunction "PGND4_17") (pintype "passive"))
      (node (ref "U5") (pin "18") (pinfunction "N.C._18") (pintype "passive"))
      (node (ref "U5") (pin "19") (pinfunction "N.C._19") (pintype "passive"))
      (node (ref "U5") (pin "2") (pinfunction "PGND3_2") (pintype "passive"))
      (node (ref "U5") (pin "25") (pinfunction "PGND2_25") (pintype "passive"))
      (node (ref "U5") (pin "26") (pinfunction "PGND2_26") (pintype "passive"))
      (node (ref "U5") (pin "3") (pinfunction "PGND3_3") (pintype "passive"))
      (node (ref "U5") (pin "30") (pinfunction "PGND1_30") (pintype "passive"))
      (node (ref "U5") (pin "31") (pinfunction "PGND1_31") (pintype "passive"))
      (node (ref "U5") (pin "36") (pinfunction "N.C._36") (pintype "passive"))
      (node (ref "U6") (pin "1") (pinfunction "N.C._1") (pintype "passive"))
      (node (ref "U6") (pin "16") (pinfunction "PGND4_16") (pintype "passive"))
      (node (ref "U6") (pin "17") (pinfunction "PGND4_17") (pintype "passive"))
      (node (ref "U6") (pin "18") (pinfunction "N.C._18") (pintype "passive"))
      (node (ref "U6") (pin "19") (pinfunction "N.C._19") (pintype "passive"))
      (node (ref "U6") (pin "2") (pinfunction "PGND3_2") (pintype "passive"))
      (node (ref "U6") (pin "25") (pinfunction "PGND2_25") (pintype "passive"))
      (node (ref "U6") (pin "26") (pinfunction "PGND2_26") (pintype "passive"))
      (node (ref "U6") (pin "3") (pinfunction "PGND3_3") (pintype "passive"))
      (node (ref "U6") (pin "30") (pinfunction "PGND1_30") (pintype "passive"))
      (node (ref "U6") (pin "31") (pinfunction "PGND1_31") (pintype "passive"))
      (node (ref "U6") (pin "36") (pinfunction "N.C._36") (pintype "passive"))
      (node (ref "VT3") (pin "3") (pinfunction "3_3") (pintype "passive"))
    )
    (net (code "75") (name "unconnected-(J6-Pad4)") (class "Default")
      (node (ref "J6") (pin "4") (pinfunction "4_4") (pintype "passive"))
    )
    (net (code "76") (name "unconnected-(J6-Pad10)") (class "Default")
      (node (ref "J6") (pin "10") (pinfunction "10_10") (pintype "passive"))
    )
    (net (code "77") (name "unconnected-(U2-N.C.-Pad29)") (class "Default")
      (node (ref "U2") (pin "29") (pinfunction "N.C._29") (pintype "passive"))
    )
    (net (code "78") (name "unconnected-(U3-D3-Pad6)") (class "Default")
      (node (ref "U3") (pin "6") (pinfunction "D3_6") (pintype "output+no_connect"))
    )
    (net (code "79") (name "unconnected-(U3-D3-Pad7)") (class "Default")
      (node (ref "U3") (pin "7") (pinfunction "D3_7") (pintype "output+no_connect"))
    )
    (net (code "80") (name "unconnected-(U3-IN3-Pad33)") (class "Default")
      (node (ref "U3") (pin "33") (pinfunction "IN3_33") (pintype "passive+no_connect"))
    )
    (net (code "81") (name "unconnected-(U3-N.C.-Pad29)") (class "Default")
      (node (ref "U3") (pin "29") (pinfunction "N.C._29") (pintype "passive"))
    )
    (net (code "82") (name "unconnected-(U3-Q3-Pad4)") (class "Default")
      (node (ref "U3") (pin "4") (pinfunction "Q3_4") (pintype "input+no_connect"))
    )
    (net (code "83") (name "unconnected-(U3-Q3-Pad5)") (class "Default")
      (node (ref "U3") (pin "5") (pinfunction "Q3_5") (pintype "input+no_connect"))
    )
    (net (code "84") (name "unconnected-(U3-ST3-Pad35)") (class "Default")
      (node (ref "U3") (pin "35") (pinfunction "ST3_35") (pintype "passive+no_connect"))
    )
    (net (code "85") (name "unconnected-(U5-IN2-Pad21)") (class "Default")
      (node (ref "U5") (pin "21") (pinfunction "IN2_21") (pintype "passive+no_connect"))
    )
    (net (code "86") (name "unconnected-(U5-N.C.-Pad29)") (class "Default")
      (node (ref "U5") (pin "29") (pinfunction "N.C._29") (pintype "passive"))
    )
    (net (code "87") (name "unconnected-(U5-Q2-Pad10)") (class "Default")
      (node (ref "U5") (pin "10") (pinfunction "Q2_10") (pintype "input+no_connect"))
    )
    (net (code "88") (name "unconnected-(U5-Q2-Pad11)") (class "Default")
      (node (ref "U5") (pin "11") (pinfunction "Q2_11") (pintype "input+no_connect"))
    )
    (net (code "89") (name "unconnected-(U5-ST2-Pad23)") (class "Default")
      (node (ref "U5") (pin "23") (pinfunction "ST2_23") (pintype "passive+no_connect"))
    )
    (net (code "90") (name "unconnected-(U6-N.C.-Pad29)") (class "Default")
      (node (ref "U6") (pin "29") (pinfunction "N.C._29") (pintype "passive"))
    )
  )
)
